# head_board.net
KiCad netlist of a schematic drawn in EAGLE
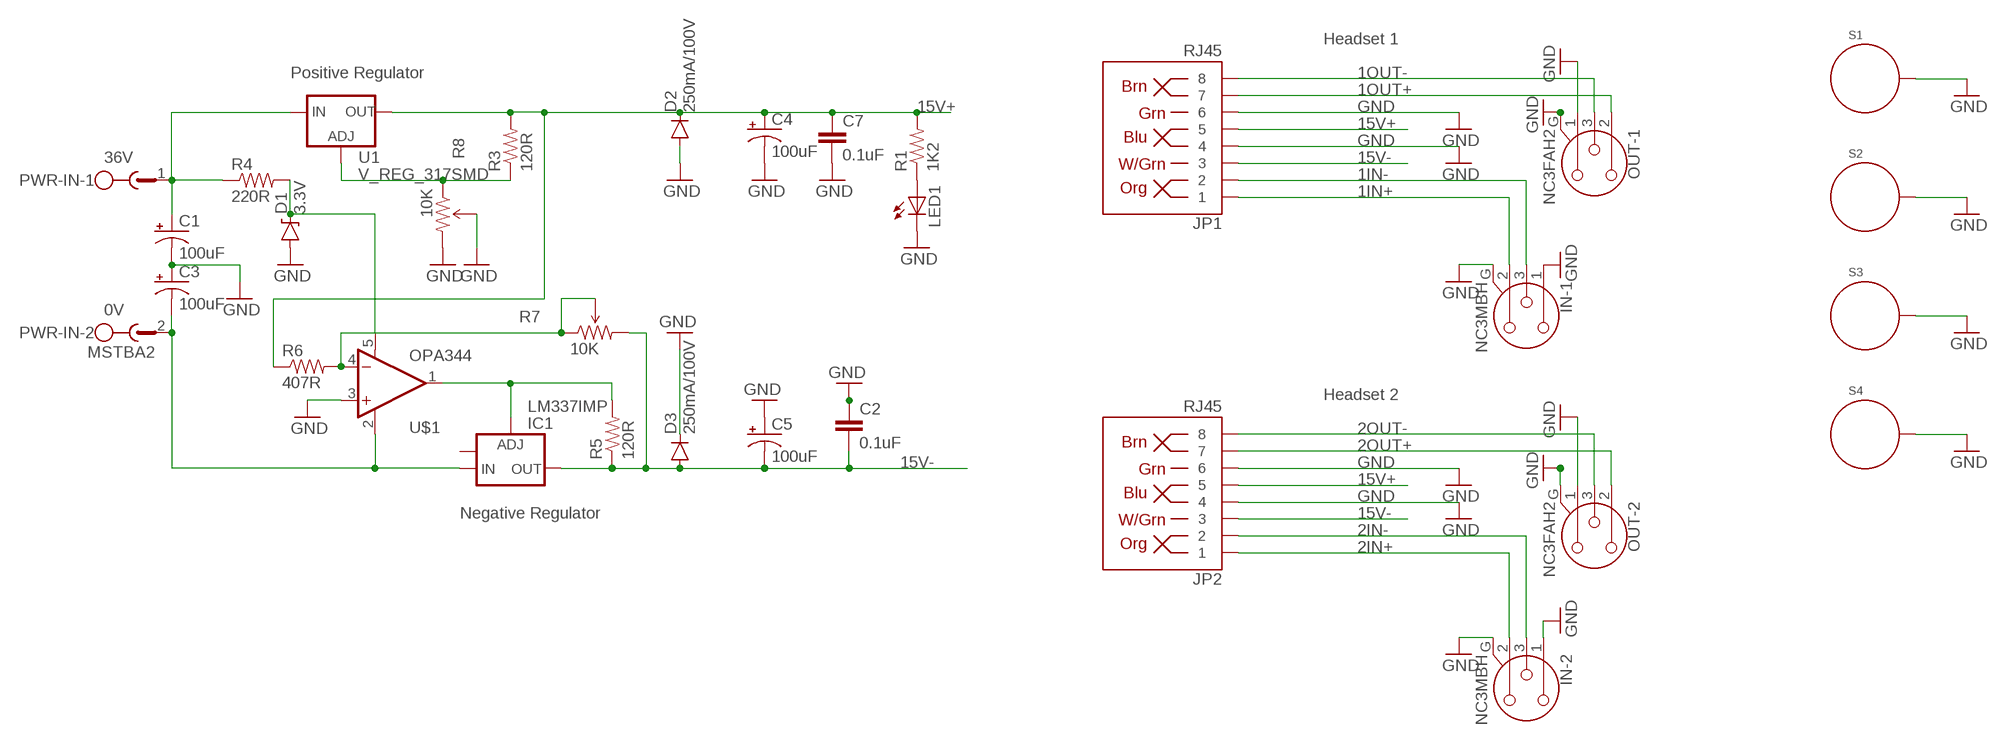
[diagram p0: schematic, sheet 1]

(export (version "E")
  (design (tool "Eeschema 10.0.6"))
  (components
    (comp (ref "C1")
      (value "100uF")
      (footprint "eagle-import:CPOL-RADIAL-100UF-25V")
      (libsource (lib "eagle-import") (part "CAP_POLPTH1"))
    )
    (comp (ref "C2")
      (value "0.1uF")
      (footprint "eagle-import:0603-CAP")
      (libsource (lib "eagle-import") (part "0.1UF-25V-5%(0603)"))
    )
    (comp (ref "C3")
      (value "100uF")
      (footprint "eagle-import:CPOL-RADIAL-100UF-25V")
      (libsource (lib "eagle-import") (part "CAP_POLPTH1"))
    )
    (comp (ref "C4")
      (value "100uF")
      (footprint "eagle-import:CPOL-RADIAL-100UF-25V")
      (libsource (lib "eagle-import") (part "CAP_POLPTH1"))
    )
    (comp (ref "C5")
      (value "100uF")
      (footprint "eagle-import:CPOL-RADIAL-100UF-25V")
      (libsource (lib "eagle-import") (part "CAP_POLPTH1"))
    )
    (comp (ref "C7")
      (value "0.1uF")
      (footprint "eagle-import:0603-CAP")
      (libsource (lib "eagle-import") (part "0.1UF-25V-5%(0603)"))
    )
    (comp (ref "D1")
      (value "3.3V")
      (footprint "eagle-import:SOD-323")
      (libsource (lib "eagle-import") (part "DIODE-ZENER3.3V"))
    )
    (comp (ref "D2")
      (value "250mA/100V")
      (footprint "eagle-import:SOD-323")
      (libsource (lib "eagle-import") (part "DIODEBAS16"))
    )
    (comp (ref "D3")
      (value "250mA/100V")
      (footprint "eagle-import:SOD-323")
      (libsource (lib "eagle-import") (part "DIODEBAS16"))
    )
    (comp (ref "IC1")
      (value "LM337IMP")
      (footprint "eagle-import:SOT-223")
      (libsource (lib "eagle-import") (part "LM337IMP"))
    )
    (comp (ref "IN-1")
      (value "NC3MBH")
      (footprint "eagle-import:NC3MBH")
      (fields (field (name "MF") "NEUTRIK"))
      (libsource (lib "eagle-import") (part "NC3MBH"))
    )
    (comp (ref "IN-2")
      (value "NC3MBH")
      (footprint "eagle-import:NC3MBH")
      (fields (field (name "MF") "NEUTRIK"))
      (libsource (lib "eagle-import") (part "NC3MBH"))
    )
    (comp (ref "JP1")
      (value "RJ45")
      (footprint "eagle-import:RJ45-8")
      (libsource (lib "eagle-import") (part "RJ45-8PTH"))
    )
    (comp (ref "JP2")
      (value "RJ45")
      (footprint "eagle-import:RJ45-8")
      (libsource (lib "eagle-import") (part "RJ45-8PTH"))
    )
    (comp (ref "LED1")
      (value "LEDCHIPLED_0805")
      (footprint "eagle-import:CHIPLED_0805")
      (libsource (lib "eagle-import") (part "LEDCHIPLED_0805"))
    )
    (comp (ref "OUT-1")
      (value "NC3FAH2")
      (footprint "eagle-import:NC3FAH2")
      (libsource (lib "eagle-import") (part "NC3FAH2"))
    )
    (comp (ref "OUT-2")
      (value "NC3FAH2")
      (footprint "eagle-import:NC3FAH2")
      (libsource (lib "eagle-import") (part "NC3FAH2"))
    )
    (comp (ref "PWR-IN")
      (value "MSTBA2")
      (footprint "eagle-import:MSTBA2")
      (fields (field (name "MF") "FARNELL") (field (name "MPN") "1757242"))
      (libsource (lib "eagle-import") (part "MSTBA2"))
    )
    (comp (ref "R1")
      (value "1K2")
      (footprint "eagle-import:0603-RES")
      (libsource (lib "eagle-import") (part "RESISTOR0603-RES"))
    )
    (comp (ref "R3")
      (value "120R")
      (footprint "eagle-import:0603-RES")
      (libsource (lib "eagle-import") (part "RESISTOR0603-RES"))
    )
    (comp (ref "R4")
      (value "220R")
      (footprint "eagle-import:0603-RES")
      (libsource (lib "eagle-import") (part "RESISTOR0603-RES"))
    )
    (comp (ref "R5")
      (value "120R")
      (footprint "eagle-import:0603-RES")
      (libsource (lib "eagle-import") (part "RESISTOR0603-RES"))
    )
    (comp (ref "R6")
      (value "407R")
      (footprint "eagle-import:0603-RES")
      (libsource (lib "eagle-import") (part "RESISTOR0603-RES"))
    )
    (comp (ref "R7")
      (value "10K")
      (footprint "eagle-import:TRIMPOT_TC33")
      (libsource (lib "eagle-import") (part "TRIMPOT-2"))
    )
    (comp (ref "R8")
      (value "10K")
      (footprint "eagle-import:TRIMPOT_TC33")
      (libsource (lib "eagle-import") (part "TRIMPOT-2"))
    )
    (comp (ref "S1")
      (value "STANDOFF_ELECTRICAL")
      (footprint "eagle-import:STANDOFF-ELECTRICAL")
      (libsource (lib "eagle-import") (part "STANDOFF_ELECTRICAL"))
    )
    (comp (ref "S2")
      (value "STANDOFF_ELECTRICAL")
      (footprint "eagle-import:STANDOFF-ELECTRICAL")
      (libsource (lib "eagle-import") (part "STANDOFF_ELECTRICAL"))
    )
    (comp (ref "S3")
      (value "STANDOFF_ELECTRICAL")
      (footprint "eagle-import:STANDOFF-ELECTRICAL")
      (libsource (lib "eagle-import") (part "STANDOFF_ELECTRICAL"))
    )
    (comp (ref "S4")
      (value "STANDOFF_ELECTRICAL")
      (footprint "eagle-import:STANDOFF-ELECTRICAL")
      (libsource (lib "eagle-import") (part "STANDOFF_ELECTRICAL"))
    )
    (comp (ref "U$1")
      (value "OPA344")
      (footprint "eagle-import:SOT23-5")
      (libsource (lib "eagle-import") (part "OPA344"))
    )
    (comp (ref "U1")
      (value "V_REG_317SMD")
      (footprint "eagle-import:SOT223")
      (libsource (lib "eagle-import") (part "V_REG_317SMD"))
    )
  )
  (nets
    (net (code "1") (name "/1IN+") (class "Default")
      (node (ref "IN-1") (pin "2") (pinfunction "2_2") (pintype "passive"))
      (node (ref "JP1") (pin "1") (pinfunction "1_1") (pintype "bidirectional"))
    )
    (net (code "2") (name "/1IN-") (class "Default")
      (node (ref "IN-1") (pin "3") (pinfunction "3_3") (pintype "passive"))
      (node (ref "JP1") (pin "2") (pinfunction "2_2") (pintype "bidirectional"))
    )
    (net (code "3") (name "/1OUT+") (class "Default")
      (node (ref "JP1") (pin "7") (pinfunction "7_7") (pintype "bidirectional"))
      (node (ref "OUT-1") (pin "2") (pinfunction "1_2") (pintype "passive"))
    )
    (net (code "4") (name "/1OUT-") (class "Default")
      (node (ref "JP1") (pin "8") (pinfunction "8_8") (pintype "bidirectional"))
      (node (ref "OUT-1") (pin "3") (pinfunction "3_3") (pintype "passive"))
    )
    (net (code "5") (name "/2IN+") (class "Default")
      (node (ref "IN-2") (pin "2") (pinfunction "2_2") (pintype "passive"))
      (node (ref "JP2") (pin "1") (pinfunction "1_1") (pintype "bidirectional"))
    )
    (net (code "6") (name "/2IN-") (class "Default")
      (node (ref "IN-2") (pin "3") (pinfunction "3_3") (pintype "passive"))
      (node (ref "JP2") (pin "2") (pinfunction "2_2") (pintype "bidirectional"))
    )
    (net (code "7") (name "/2OUT+") (class "Default")
      (node (ref "JP2") (pin "7") (pinfunction "7_7") (pintype "bidirectional"))
      (node (ref "OUT-2") (pin "2") (pinfunction "1_2") (pintype "passive"))
    )
    (net (code "8") (name "/2OUT-") (class "Default")
      (node (ref "JP2") (pin "8") (pinfunction "8_8") (pintype "bidirectional"))
      (node (ref "OUT-2") (pin "3") (pinfunction "3_3") (pintype "passive"))
    )
    (net (code "9") (name "/15V+") (class "Default")
      (node (ref "C4") (pin "1") (pinfunction "+_1") (pintype "passive"))
      (node (ref "C7") (pin "1") (pinfunction "1_1") (pintype "passive"))
      (node (ref "D2") (pin "C") (pinfunction "C_C") (pintype "passive"))
      (node (ref "JP1") (pin "5") (pinfunction "5_5") (pintype "bidirectional"))
      (node (ref "JP2") (pin "5") (pinfunction "5_5") (pintype "bidirectional"))
      (node (ref "R1") (pin "2") (pinfunction "2_2") (pintype "passive"))
      (node (ref "R3") (pin "2") (pinfunction "2_2") (pintype "passive"))
      (node (ref "R6") (pin "1") (pinfunction "1_1") (pintype "passive"))
      (node (ref "U1") (pin "2") (pinfunction "OUT_2") (pintype "output"))
    )
    (net (code "10") (name "/15V-") (class "Default")
      (node (ref "C2") (pin "2") (pinfunction "2_2") (pintype "passive"))
      (node (ref "C5") (pin "2") (pinfunction "-_2") (pintype "passive"))
      (node (ref "D3") (pin "A") (pinfunction "A_A") (pintype "passive"))
      (node (ref "IC1") (pin "3") (pinfunction "OUT_3") (pintype "passive"))
      (node (ref "JP1") (pin "3") (pinfunction "3_3") (pintype "bidirectional"))
      (node (ref "JP2") (pin "3") (pinfunction "3_3") (pintype "bidirectional"))
      (node (ref "R5") (pin "1") (pinfunction "1_1") (pintype "passive"))
      (node (ref "R7") (pin "3") (pinfunction "CW_3") (pintype "passive"))
    )
    (net (code "11") (name "GND") (class "Default")
      (node (ref "C1") (pin "2") (pinfunction "-_2") (pintype "passive"))
      (node (ref "C2") (pin "1") (pinfunction "1_1") (pintype "passive"))
      (node (ref "C3") (pin "1") (pinfunction "+_1") (pintype "passive"))
      (node (ref "C4") (pin "2") (pinfunction "-_2") (pintype "passive"))
      (node (ref "C5") (pin "1") (pinfunction "+_1") (pintype "passive"))
      (node (ref "C7") (pin "2") (pinfunction "2_2") (pintype "passive"))
      (node (ref "D1") (pin "A") (pinfunction "A_A") (pintype "passive"))
      (node (ref "D2") (pin "A") (pinfunction "A_A") (pintype "passive"))
      (node (ref "D3") (pin "C") (pinfunction "C_C") (pintype "passive"))
      (node (ref "IN-1") (pin "1") (pinfunction "1_1") (pintype "passive"))
      (node (ref "IN-1") (pin "G") (pinfunction "G_G") (pintype "passive"))
      (node (ref "IN-2") (pin "1") (pinfunction "1_1") (pintype "passive"))
      (node (ref "IN-2") (pin "G") (pinfunction "G_G") (pintype "passive"))
      (node (ref "JP1") (pin "4") (pinfunction "4_4") (pintype "bidirectional"))
      (node (ref "JP1") (pin "6") (pinfunction "6_6") (pintype "bidirectional"))
      (node (ref "JP2") (pin "4") (pinfunction "4_4") (pintype "bidirectional"))
      (node (ref "JP2") (pin "6") (pinfunction "6_6") (pintype "bidirectional"))
      (node (ref "LED1") (pin "C") (pinfunction "C_C") (pintype "passive"))
      (node (ref "OUT-1") (pin "1") (pinfunction "2_1") (pintype "passive"))
      (node (ref "OUT-1") (pin "G") (pinfunction "G_G") (pintype "passive"))
      (node (ref "OUT-2") (pin "1") (pinfunction "2_1") (pintype "passive"))
      (node (ref "OUT-2") (pin "G") (pinfunction "G_G") (pintype "passive"))
      (node (ref "R8") (pin "2") (pinfunction "WIPER_2") (pintype "passive"))
      (node (ref "R8") (pin "3") (pinfunction "CW_3") (pintype "passive"))
      (node (ref "S1") (pin "P1") (pinfunction "P$1_P1") (pintype "bidirectional"))
      (node (ref "S2") (pin "P1") (pinfunction "P$1_P1") (pintype "bidirectional"))
      (node (ref "S3") (pin "P1") (pinfunction "P$1_P1") (pintype "bidirectional"))
      (node (ref "S4") (pin "P1") (pinfunction "P$1_P1") (pintype "bidirectional"))
      (node (ref "U$1") (pin "3") (pinfunction "+IN_3") (pintype "input"))
    )
    (net (code "12") (name "Net-(C1-+)") (class "Default")
      (node (ref "C1") (pin "1") (pinfunction "+_1") (pintype "passive"))
      (node (ref "PWR-IN") (pin "1") (pinfunction "1_1") (pintype "passive"))
      (node (ref "R4") (pin "1") (pinfunction "1_1") (pintype "passive"))
      (node (ref "U1") (pin "3") (pinfunction "IN_3") (pintype "input"))
    )
    (net (code "13") (name "Net-(C3--)") (class "Default")
      (node (ref "C3") (pin "2") (pinfunction "-_2") (pintype "passive"))
      (node (ref "IC1") (pin "2") (pinfunction "IN_2") (pintype "input"))
      (node (ref "PWR-IN") (pin "2") (pinfunction "1_2") (pintype "passive"))
      (node (ref "U$1") (pin "2") (pinfunction "V-_2") (pintype "power_in"))
    )
    (net (code "14") (name "Net-(IC1-ADJ)") (class "Default")
      (node (ref "IC1") (pin "1") (pinfunction "ADJ_1") (pintype "input"))
      (node (ref "R5") (pin "2") (pinfunction "2_2") (pintype "passive"))
      (node (ref "U$1") (pin "1") (pinfunction "OUT_1") (pintype "output"))
    )
    (net (code "15") (name "Net-(LED1-PadA)") (class "Default")
      (node (ref "LED1") (pin "A") (pinfunction "A_A") (pintype "passive"))
      (node (ref "R1") (pin "1") (pinfunction "1_1") (pintype "passive"))
    )
    (net (code "16") (name "Net-(R7-CCW)") (class "Default")
      (node (ref "R6") (pin "2") (pinfunction "2_2") (pintype "passive"))
      (node (ref "R7") (pin "1") (pinfunction "CCW_1") (pintype "passive"))
      (node (ref "R7") (pin "2") (pinfunction "WIPER_2") (pintype "passive"))
      (node (ref "U$1") (pin "4") (pinfunction "-IN_4") (pintype "input"))
    )
    (net (code "17") (name "Net-(R8-CCW)") (class "Default")
      (node (ref "R3") (pin "1") (pinfunction "1_1") (pintype "passive"))
      (node (ref "R8") (pin "1") (pinfunction "CCW_1") (pintype "passive"))
      (node (ref "U1") (pin "1") (pinfunction "ADJ_1") (pintype "input"))
    )
    (net (code "18") (name "Net-(U$1-V+)") (class "Default")
      (node (ref "D1") (pin "C") (pinfunction "C_C") (pintype "passive"))
      (node (ref "R4") (pin "2") (pinfunction "2_2") (pintype "passive"))
      (node (ref "U$1") (pin "5") (pinfunction "V+_5") (pintype "power_in"))
    )
    (net (code "19") (name "unconnected-(IC1-P$1-Pad4)") (class "Default")
      (node (ref "IC1") (pin "4") (pinfunction "P$1_4") (pintype "bidirectional"))
    )
  )
)
